# STM32F407.net
KiCad netlist of a schematic drawn in Altium Designer
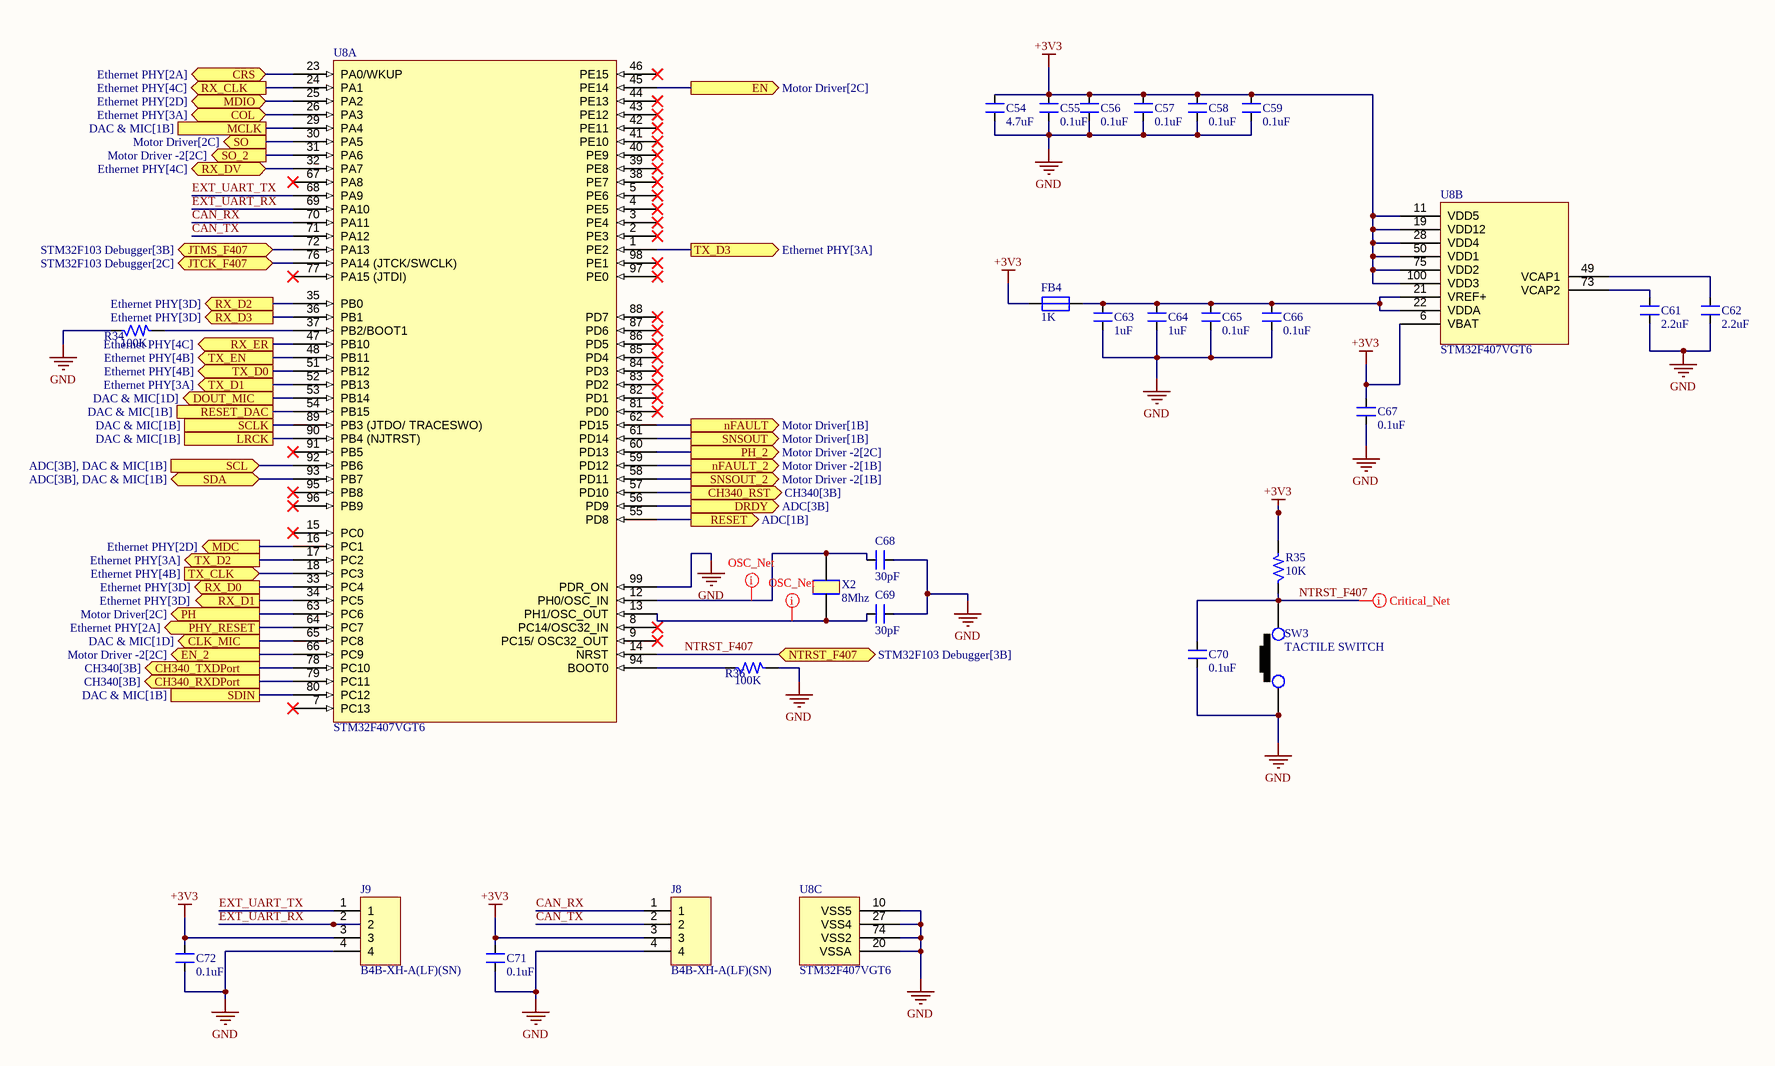
[diagram p0: STM32F407.SchDoc]

(export (version "E")
  (design (tool "Eeschema 10.0.6"))
  (components
    (comp (ref "C54")
      (value "4.7uF")
      (footprint "CAP_0805")
      (description "4.7µF ±10% 50V Ceramic Capacitor X5R 0805 (2012 Metric)")
      (fields
        (field (name "MANUFACTURER") "Yageo")
        (field (name "MANUFACTURER PART NUMBER") "GRM21BR61H475KE51L")
      )
      (libsource (lib "ESTEEMPCBLIB") (part "CAP_4.7uF-50V-10%-0805"))
    )
    (comp (ref "C55")
      (value "0.1uF")
      (footprint "CAP_0805")
      (description "0.1µF ±10% 50V Ceramic Capacitor X7R 0805 (2012 Metric)")
      (fields
        (field (name "MANUFACTURER") "Samsung")
        (field (name "MANUFACTURER PART NUMBER") "CL21B104KBCNNNC")
      )
      (libsource (lib "ESTEEMPCBLIB") (part "CAP_0.1uF-50V-10%-0805"))
    )
    (comp (ref "C56")
      (value "0.1uF")
      (footprint "CAP_0805")
      (description "0.1µF ±10% 50V Ceramic Capacitor X7R 0805 (2012 Metric)")
      (fields
        (field (name "MANUFACTURER") "Samsung")
        (field (name "MANUFACTURER PART NUMBER") "CL21B104KBCNNNC")
      )
      (libsource (lib "ESTEEMPCBLIB") (part "CAP_0.1uF-50V-10%-0805"))
    )
    (comp (ref "C57")
      (value "0.1uF")
      (footprint "CAP_0805")
      (description "0.1µF ±10% 50V Ceramic Capacitor X7R 0805 (2012 Metric)")
      (fields
        (field (name "MANUFACTURER") "Samsung")
        (field (name "MANUFACTURER PART NUMBER") "CL21B104KBCNNNC")
      )
      (libsource (lib "ESTEEMPCBLIB") (part "CAP_0.1uF-50V-10%-0805"))
    )
    (comp (ref "C58")
      (value "0.1uF")
      (footprint "CAP_0805")
      (description "0.1µF ±10% 50V Ceramic Capacitor X7R 0805 (2012 Metric)")
      (fields
        (field (name "MANUFACTURER") "Samsung")
        (field (name "MANUFACTURER PART NUMBER") "CL21B104KBCNNNC")
      )
      (libsource (lib "ESTEEMPCBLIB") (part "CAP_0.1uF-50V-10%-0805"))
    )
    (comp (ref "C59")
      (value "0.1uF")
      (footprint "CAP_0805")
      (description "0.1µF ±10% 50V Ceramic Capacitor X7R 0805 (2012 Metric)")
      (fields
        (field (name "MANUFACTURER") "Samsung")
        (field (name "MANUFACTURER PART NUMBER") "CL21B104KBCNNNC")
      )
      (libsource (lib "ESTEEMPCBLIB") (part "CAP_0.1uF-50V-10%-0805"))
    )
    (comp (ref "C61")
      (value "2.2uF")
      (footprint "CAP_0805")
      (description "2.2µF ±10% 25V Ceramic Capacitor X7R 0805 (2012 Metric)")
      (fields
        (field (name "MANUFACTURER") "KEMET")
        (field (name "MANUFACTURER PART NUMBER") "CL21B225KAFNFNE")
      )
      (libsource (lib "ESTEEMPCBLIB") (part "CAP_2.2uF-25V-10%-0805"))
    )
    (comp (ref "C62")
      (value "2.2uF")
      (footprint "CAP_0805")
      (description "2.2µF ±10% 25V Ceramic Capacitor X7R 0805 (2012 Metric)")
      (fields
        (field (name "MANUFACTURER") "KEMET")
        (field (name "MANUFACTURER PART NUMBER") "CL21B225KAFNFNE")
      )
      (libsource (lib "ESTEEMPCBLIB") (part "CAP_2.2uF-25V-10%-0805"))
    )
    (comp (ref "C63")
      (value "1uF")
      (footprint "CAP_0805")
      (description "1µF ±5% 50V Ceramic Capacitor X7R 0805 (2012 Metric)")
      (fields
        (field (name "MANUFACTURER") "Samsung")
        (field (name "MANUFACTURER PART NUMBER") "CC0805JKX7R9BB105")
      )
      (libsource (lib "ESTEEMPCBLIB") (part "CAP_1uF-50V-5%-0805"))
    )
    (comp (ref "C64")
      (value "1uF")
      (footprint "CAP_0805")
      (description "1µF ±5% 50V Ceramic Capacitor X7R 0805 (2012 Metric)")
      (fields
        (field (name "MANUFACTURER") "Samsung")
        (field (name "MANUFACTURER PART NUMBER") "CC0805JKX7R9BB105")
      )
      (libsource (lib "ESTEEMPCBLIB") (part "CAP_1uF-50V-5%-0805"))
    )
    (comp (ref "C65")
      (value "0.1uF")
      (footprint "CAP_0805")
      (description "0.1µF ±10% 50V Ceramic Capacitor X7R 0805 (2012 Metric)")
      (fields
        (field (name "MANUFACTURER") "Samsung")
        (field (name "MANUFACTURER PART NUMBER") "CL21B104KBCNNNC")
      )
      (libsource (lib "ESTEEMPCBLIB") (part "CAP_0.1uF-50V-10%-0805"))
    )
    (comp (ref "C66")
      (value "0.1uF")
      (footprint "CAP_0805")
      (description "0.1µF ±10% 50V Ceramic Capacitor X7R 0805 (2012 Metric)")
      (fields
        (field (name "MANUFACTURER") "Samsung")
        (field (name "MANUFACTURER PART NUMBER") "CL21B104KBCNNNC")
      )
      (libsource (lib "ESTEEMPCBLIB") (part "CAP_0.1uF-50V-10%-0805"))
    )
    (comp (ref "C67")
      (value "0.1uF")
      (footprint "CAP_0805")
      (description "0.1µF ±10% 50V Ceramic Capacitor X7R 0805 (2012 Metric)")
      (fields
        (field (name "MANUFACTURER") "Samsung")
        (field (name "MANUFACTURER PART NUMBER") "CL21B104KBCNNNC")
      )
      (libsource (lib "ESTEEMPCBLIB") (part "CAP_0.1uF-50V-10%-0805"))
    )
    (comp (ref "C68")
      (value "30pF")
      (footprint "CAP_0805")
      (description "±10% 50V Ceramic Capacitor C0G, NP0 0805 (2012 Metric)")
      (fields
        (field (name "MANUFACTURER PART NUMBER") "C0805C300K5GAC7800")
        (field (name "MANUFACTURER") "KEMET")
      )
      (libsource (lib "ESTEEMPCBLIB") (part "CAP_30pF-50V-10%-0805"))
    )
    (comp (ref "C69")
      (value "30pF")
      (footprint "CAP_0805")
      (description "±10% 50V Ceramic Capacitor C0G, NP0 0805 (2012 Metric)")
      (fields
        (field (name "MANUFACTURER PART NUMBER") "C0805C300K5GAC7800")
        (field (name "MANUFACTURER") "KEMET")
      )
      (libsource (lib "ESTEEMPCBLIB") (part "CAP_30pF-50V-10%-0805"))
    )
    (comp (ref "C70")
      (value "0.1uF")
      (footprint "CAP_0805")
      (description "0.1µF ±10% 50V Ceramic Capacitor X7R 0805 (2012 Metric)")
      (fields
        (field (name "MANUFACTURER") "Samsung")
        (field (name "MANUFACTURER PART NUMBER") "CL21B104KBCNNNC")
      )
      (libsource (lib "ESTEEMPCBLIB") (part "CAP_0.1uF-50V-10%-0805"))
    )
    (comp (ref "C71")
      (value "0.1uF")
      (footprint "CAP_0805")
      (description "0.1µF ±10% 50V Ceramic Capacitor X7R 0805 (2012 Metric)")
      (fields
        (field (name "MANUFACTURER") "Samsung")
        (field (name "MANUFACTURER PART NUMBER") "CL21B104KBCNNNC")
      )
      (libsource (lib "ESTEEMPCBLIB") (part "CAP_0.1uF-50V-10%-0805"))
    )
    (comp (ref "C72")
      (value "0.1uF")
      (footprint "CAP_0805")
      (description "0.1µF ±10% 50V Ceramic Capacitor X7R 0805 (2012 Metric)")
      (fields
        (field (name "MANUFACTURER") "Samsung")
        (field (name "MANUFACTURER PART NUMBER") "CL21B104KBCNNNC")
      )
      (libsource (lib "ESTEEMPCBLIB") (part "CAP_0.1uF-50V-10%-0805"))
    )
    (comp (ref "FB4")
      (value "1K")
      (footprint "IND_0805")
      (description "1 kOhms @ 100MHz 1 Power Line Ferrite Bead 0805 (2012 Metric) 1.6A")
      (fields
        (field (name "MANUFACTURER") "Laird")
        (field (name "MANUFACTURER PART NUMBER") "BLM21SP102SH1D")
      )
      (libsource (lib "ESTEEMPCBLIB") (part "FB_1K-100MHZ-1.6A-0805"))
    )
    (comp (ref "J8")
      (value "B4B-XH-A(LF)(SN)")
      (footprint "CON4_100_B4B-XH-A_TH_ST")
      (description "4 Pins, 1 Row 2.54mm Pitch, straight Connector, male")
      (fields (field (name "MANUFACTURER") "Wurth Electronics") (field (name "MATING PART NUMBER") "XHP-4"))
      (libsource (lib "ESTEEMPCBLIB") (part "CON-PLG_4X1-100-ST-TH"))
    )
    (comp (ref "J9")
      (value "B4B-XH-A(LF)(SN)")
      (footprint "CON4_100_B4B-XH-A_TH_ST")
      (description "4 Pins, 1 Row 2.54mm Pitch, straight Connector, male")
      (fields (field (name "MANUFACTURER") "Wurth Electronics") (field (name "MATING PART NUMBER") "XHP-4"))
      (libsource (lib "ESTEEMPCBLIB") (part "CON-PLG_4X1-100-ST-TH"))
    )
    (comp (ref "R34")
      (value "100K")
      (footprint "RES_0603")
      (description "100 kOhms ±1% 0.1W, 1/10W Chip Resistor 0603 (1608 Metric) Automotive AEC-Q200 Thick Film")
      (fields
        (field (name "MANUFACTURER") "Stackpole Electronics")
        (field (name "MANUFACTURER PART NUMBER") "RMCF0603FT100K")
      )
      (libsource (lib "ESTEEMPCBLIB") (part "RES_100K-0.1W-1%-0603"))
    )
    (comp (ref "R35")
      (value "10K")
      (footprint "RES_0603")
      (description "10 kOhms ±1% 0.1W, 1/10W Chip Resistor 0603 (1608 Metric) Automotive AEC-Q200 Thick Film")
      (fields (field (name "MANUFACTURER") "Walsin") (field (name "MANUFACTURER PART NUMBER") "WR06X1002FTL"))
      (libsource (lib "ESTEEMPCBLIB") (part "RES_10K-0.1W-1%-0603"))
    )
    (comp (ref "R36")
      (value "100K")
      (footprint "RES_0603")
      (description "100 kOhms ±1% 0.1W, 1/10W Chip Resistor 0603 (1608 Metric) Automotive AEC-Q200 Thick Film")
      (fields
        (field (name "MANUFACTURER") "Stackpole Electronics")
        (field (name "MANUFACTURER PART NUMBER") "RMCF0603FT100K")
      )
      (libsource (lib "ESTEEMPCBLIB") (part "RES_100K-0.1W-1%-0603"))
    )
    (comp (ref "SW3")
      (value "TACTILE SWITCH")
      (footprint "SW_342_SMD")
      (description "Tactile Switch SPST-NO Top Actuated Surface Mount")
      (fields
        (field (name "MANUFACTURER") "ITT C&K")
        (field (name "MANUFACTURER PART NUMBER") "RS-282G05A3-SMRT")
      )
      (libsource (lib "ESTEEMPCBLIB") (part "SW1_RS-282G05A3-SMRT-SMD"))
    )
    (comp (ref "U8")
      (value "STM32F407VGT6")
      (footprint "QFN100_19.6_669_58X10_SMD")
      (description "ARM® Cortex®-M4 STM32F4 Microcontroller IC 32-Bit 168MHz 1MB (1M x 8) FLASH 100-LQFP (14x14)")
      (fields (field (name "MANUFACTURER") "STMicroelectronics"))
      (libsource (lib "ESTEEMPCBLIB") (part "IC_STM32F407VGT6"))
    )
    (comp (ref "X2")
      (value "8Mhz")
      (footprint "XTAL_314_240X47_SMD")
      (description "8MHz ±30ppm Crystal 32pF 60 Ohms HC-49/US")
      (fields
        (field (name "MANUFACTURER") "Fox Electronics")
        (field (name "MANUFACTURER PART NUMBER") "ECS-80-32-5PX-TR")
      )
      (libsource (lib "ESTEEMPCBLIB") (part "XTAL_8MHZ-ECS-80-32-5PX-SMD"))
    )
  )
  (nets
    (net (code "1") (name "+3V3") (class "Default")
      (node (ref "C54") (pin "2") (pinfunction "2_2") (pintype "passive"))
      (node (ref "C55") (pin "2") (pinfunction "2_2") (pintype "passive"))
      (node (ref "C56") (pin "2") (pinfunction "2_2") (pintype "passive"))
      (node (ref "C57") (pin "2") (pinfunction "2_2") (pintype "passive"))
      (node (ref "C58") (pin "2") (pinfunction "2_2") (pintype "passive"))
      (node (ref "C59") (pin "2") (pinfunction "2_2") (pintype "passive"))
      (node (ref "C67") (pin "2") (pinfunction "2_2") (pintype "passive"))
      (node (ref "C71") (pin "2") (pinfunction "2_2") (pintype "passive"))
      (node (ref "C72") (pin "2") (pinfunction "2_2") (pintype "passive"))
      (node (ref "FB4") (pin "1") (pinfunction "1_1") (pintype "passive"))
      (node (ref "J8") (pin "3") (pinfunction "3_3") (pintype "passive"))
      (node (ref "J9") (pin "3") (pinfunction "3_3") (pintype "passive"))
      (node (ref "R35") (pin "2") (pinfunction "2_2") (pintype "passive"))
      (node (ref "U8") (pin "100") (pinfunction "VDD3_100") (pintype "passive"))
      (node (ref "U8") (pin "11") (pinfunction "VDD5_11") (pintype "passive"))
      (node (ref "U8") (pin "19") (pinfunction "VDD12_19") (pintype "passive"))
      (node (ref "U8") (pin "28") (pinfunction "VDD4_28") (pintype "passive"))
      (node (ref "U8") (pin "50") (pinfunction "VDD1_50") (pintype "passive"))
      (node (ref "U8") (pin "6") (pinfunction "VBAT_6") (pintype "passive"))
      (node (ref "U8") (pin "75") (pinfunction "VDD2_75") (pintype "passive"))
    )
    (net (code "2") (name "/CAN_RX") (class "Default")
      (node (ref "J8") (pin "1") (pinfunction "1_1") (pintype "passive"))
      (node (ref "U8") (pin "70") (pinfunction "PA11_70") (pintype "input"))
    )
    (net (code "3") (name "/CAN_TX") (class "Default")
      (node (ref "J8") (pin "2") (pinfunction "2_2") (pintype "passive"))
      (node (ref "U8") (pin "71") (pinfunction "PA12_71") (pintype "input"))
    )
    (net (code "4") (name "/CH340_RST") (class "Default")
      (node (ref "U8") (pin "57") (pinfunction "PD10_57") (pintype "input"))
    )
    (net (code "5") (name "/CH340_RXDPort") (class "Default")
      (node (ref "U8") (pin "79") (pinfunction "PC11_79") (pintype "input"))
    )
    (net (code "6") (name "/CH340_TXDPort") (class "Default")
      (node (ref "U8") (pin "78") (pinfunction "PC10_78") (pintype "input"))
    )
    (net (code "7") (name "/CLK_MIC") (class "Default")
      (node (ref "U8") (pin "65") (pinfunction "PC8_65") (pintype "input"))
    )
    (net (code "8") (name "/COL") (class "Default")
      (node (ref "U8") (pin "26") (pinfunction "PA3_26") (pintype "input"))
    )
    (net (code "9") (name "/CRS") (class "Default")
      (node (ref "U8") (pin "23") (pinfunction "PA0/WKUP_23") (pintype "input"))
    )
    (net (code "10") (name "/DOUT_MIC") (class "Default")
      (node (ref "U8") (pin "53") (pinfunction "PB14_53") (pintype "input"))
    )
    (net (code "11") (name "/DRDY") (class "Default")
      (node (ref "U8") (pin "56") (pinfunction "PD9_56") (pintype "input"))
    )
    (net (code "12") (name "/EN") (class "Default")
      (node (ref "U8") (pin "45") (pinfunction "PE14_45") (pintype "input"))
    )
    (net (code "13") (name "/EN_2") (class "Default")
      (node (ref "U8") (pin "66") (pinfunction "PC9_66") (pintype "input"))
    )
    (net (code "14") (name "/EXT_UART_RX") (class "Default")
      (node (ref "J9") (pin "2") (pinfunction "2_2") (pintype "passive"))
      (node (ref "U8") (pin "69") (pinfunction "PA10_69") (pintype "input"))
    )
    (net (code "15") (name "/EXT_UART_TX") (class "Default")
      (node (ref "J9") (pin "1") (pinfunction "1_1") (pintype "passive"))
      (node (ref "U8") (pin "68") (pinfunction "PA9_68") (pintype "input"))
    )
    (net (code "16") (name "/JTCK_F407") (class "Default")
      (node (ref "U8") (pin "76") (pinfunction "PA14_(JTCK/SWCLK)_76") (pintype "input"))
    )
    (net (code "17") (name "/JTMS_F407") (class "Default")
      (node (ref "U8") (pin "72") (pinfunction "PA13_72") (pintype "input"))
    )
    (net (code "18") (name "/LRCK") (class "Default")
      (node (ref "U8") (pin "90") (pinfunction "PB4_(NJTRST)_90") (pintype "input"))
    )
    (net (code "19") (name "/MCLK") (class "Default")
      (node (ref "U8") (pin "29") (pinfunction "PA4_29") (pintype "input"))
    )
    (net (code "20") (name "/MDC") (class "Default")
      (node (ref "U8") (pin "16") (pinfunction "PC1_16") (pintype "input"))
    )
    (net (code "21") (name "/MDIO") (class "Default")
      (node (ref "U8") (pin "25") (pinfunction "PA2_25") (pintype "input"))
    )
    (net (code "22") (name "/NTRST_F407") (class "Default")
      (node (ref "C70") (pin "2") (pinfunction "2_2") (pintype "passive"))
      (node (ref "R35") (pin "1") (pinfunction "1_1") (pintype "passive"))
      (node (ref "SW3") (pin "2") (pinfunction "2_2") (pintype "passive"))
      (node (ref "U8") (pin "14") (pinfunction "NRST_14") (pintype "input"))
    )
    (net (code "23") (name "/PH") (class "Default")
      (node (ref "U8") (pin "63") (pinfunction "PC6_63") (pintype "input"))
    )
    (net (code "24") (name "/PHY_RESET") (class "Default")
      (node (ref "U8") (pin "64") (pinfunction "PC7_64") (pintype "input"))
    )
    (net (code "25") (name "/PH_2") (class "Default")
      (node (ref "U8") (pin "60") (pinfunction "PD13_60") (pintype "input"))
    )
    (net (code "26") (name "/RESET") (class "Default")
      (node (ref "U8") (pin "55") (pinfunction "PD8_55") (pintype "input"))
    )
    (net (code "27") (name "/RESET_DAC") (class "Default")
      (node (ref "U8") (pin "54") (pinfunction "PB15_54") (pintype "input"))
    )
    (net (code "28") (name "/RX_CLK") (class "Default")
      (node (ref "U8") (pin "24") (pinfunction "PA1_24") (pintype "input"))
    )
    (net (code "29") (name "/RX_D0") (class "Default")
      (node (ref "U8") (pin "33") (pinfunction "PC4_33") (pintype "input"))
    )
    (net (code "30") (name "/RX_D1") (class "Default")
      (node (ref "U8") (pin "34") (pinfunction "PC5_34") (pintype "input"))
    )
    (net (code "31") (name "/RX_D2") (class "Default")
      (node (ref "U8") (pin "35") (pinfunction "PB0_35") (pintype "input"))
    )
    (net (code "32") (name "/RX_D3") (class "Default")
      (node (ref "U8") (pin "36") (pinfunction "PB1_36") (pintype "input"))
    )
    (net (code "33") (name "/RX_DV") (class "Default")
      (node (ref "U8") (pin "32") (pinfunction "PA7_32") (pintype "input"))
    )
    (net (code "34") (name "/RX_ER") (class "Default")
      (node (ref "U8") (pin "47") (pinfunction "PB10_47") (pintype "input"))
    )
    (net (code "35") (name "/SCL") (class "Default")
      (node (ref "U8") (pin "92") (pinfunction "PB6_92") (pintype "input"))
    )
    (net (code "36") (name "/SCLK") (class "Default")
      (node (ref "U8") (pin "89") (pinfunction "PB3_(JTDO/_TRACESWO)_89") (pintype "input"))
    )
    (net (code "37") (name "/SDA") (class "Default")
      (node (ref "U8") (pin "93") (pinfunction "PB7_93") (pintype "input"))
    )
    (net (code "38") (name "/SDIN") (class "Default")
      (node (ref "U8") (pin "80") (pinfunction "PC12_80") (pintype "input"))
    )
    (net (code "39") (name "/SNSOUT") (class "Default")
      (node (ref "U8") (pin "61") (pinfunction "PD14_61") (pintype "input"))
    )
    (net (code "40") (name "/SNSOUT_2") (class "Default")
      (node (ref "U8") (pin "58") (pinfunction "PD11_58") (pintype "input"))
    )
    (net (code "41") (name "/SO") (class "Default")
      (node (ref "U8") (pin "30") (pinfunction "PA5_30") (pintype "input"))
    )
    (net (code "42") (name "/SO_2") (class "Default")
      (node (ref "U8") (pin "31") (pinfunction "PA6_31") (pintype "input"))
    )
    (net (code "43") (name "/TX_CLK") (class "Default")
      (node (ref "U8") (pin "18") (pinfunction "PC3_18") (pintype "input"))
    )
    (net (code "44") (name "/TX_D0") (class "Default")
      (node (ref "U8") (pin "51") (pinfunction "PB12_51") (pintype "input"))
    )
    (net (code "45") (name "/TX_D1") (class "Default")
      (node (ref "U8") (pin "52") (pinfunction "PB13_52") (pintype "input"))
    )
    (net (code "46") (name "/TX_D2") (class "Default")
      (node (ref "U8") (pin "17") (pinfunction "PC2_17") (pintype "input"))
    )
    (net (code "47") (name "/TX_D3") (class "Default")
      (node (ref "U8") (pin "1") (pinfunction "PE2_1") (pintype "input"))
    )
    (net (code "48") (name "/TX_EN") (class "Default")
      (node (ref "U8") (pin "48") (pinfunction "PB11_48") (pintype "input"))
    )
    (net (code "49") (name "/nFAULT") (class "Default")
      (node (ref "U8") (pin "62") (pinfunction "PD15_62") (pintype "input"))
    )
    (net (code "50") (name "/nFAULT_2") (class "Default")
      (node (ref "U8") (pin "59") (pinfunction "PD12_59") (pintype "input"))
    )
    (net (code "51") (name "GND") (class "Default")
      (node (ref "C54") (pin "1") (pinfunction "1_1") (pintype "passive"))
      (node (ref "C55") (pin "1") (pinfunction "1_1") (pintype "passive"))
      (node (ref "C56") (pin "1") (pinfunction "1_1") (pintype "passive"))
      (node (ref "C57") (pin "1") (pinfunction "1_1") (pintype "passive"))
      (node (ref "C58") (pin "1") (pinfunction "1_1") (pintype "passive"))
      (node (ref "C59") (pin "1") (pinfunction "1_1") (pintype "passive"))
      (node (ref "C61") (pin "1") (pinfunction "1_1") (pintype "passive"))
      (node (ref "C62") (pin "1") (pinfunction "1_1") (pintype "passive"))
      (node (ref "C63") (pin "1") (pinfunction "1_1") (pintype "passive"))
      (node (ref "C64") (pin "1") (pinfunction "1_1") (pintype "passive"))
      (node (ref "C65") (pin "1") (pinfunction "1_1") (pintype "passive"))
      (node (ref "C66") (pin "1") (pinfunction "1_1") (pintype "passive"))
      (node (ref "C67") (pin "1") (pinfunction "1_1") (pintype "passive"))
      (node (ref "C68") (pin "2") (pinfunction "2_2") (pintype "passive"))
      (node (ref "C69") (pin "2") (pinfunction "2_2") (pintype "passive"))
      (node (ref "C70") (pin "1") (pinfunction "1_1") (pintype "passive"))
      (node (ref "C71") (pin "1") (pinfunction "1_1") (pintype "passive"))
      (node (ref "C72") (pin "1") (pinfunction "1_1") (pintype "passive"))
      (node (ref "J8") (pin "4") (pinfunction "4_4") (pintype "passive"))
      (node (ref "J9") (pin "4") (pinfunction "4_4") (pintype "passive"))
      (node (ref "R34") (pin "1") (pinfunction "1_1") (pintype "passive"))
      (node (ref "R36") (pin "2") (pinfunction "2_2") (pintype "passive"))
      (node (ref "SW3") (pin "1") (pinfunction "1_1") (pintype "passive"))
      (node (ref "U8") (pin "10") (pinfunction "VSS5_10") (pintype "passive"))
      (node (ref "U8") (pin "20") (pinfunction "VSSA_20") (pintype "passive"))
      (node (ref "U8") (pin "27") (pinfunction "VSS4_27") (pintype "passive"))
      (node (ref "U8") (pin "74") (pinfunction "VSS2_74") (pintype "passive"))
      (node (ref "U8") (pin "99") (pinfunction "PDR_ON_99") (pintype "input"))
    )
    (net (code "52") (name "Net-(U8A-BOOT0)") (class "Default")
      (node (ref "R36") (pin "1") (pinfunction "1_1") (pintype "passive"))
      (node (ref "U8") (pin "94") (pinfunction "BOOT0_94") (pintype "input"))
    )
    (net (code "53") (name "Net-(U8A-PB2{slash}BOOT1)") (class "Default")
      (node (ref "R34") (pin "2") (pinfunction "2_2") (pintype "passive"))
      (node (ref "U8") (pin "37") (pinfunction "PB2/BOOT1_37") (pintype "input"))
    )
    (net (code "54") (name "Net-(U8A-PH0{slash}OSC_IN)") (class "Default")
      (node (ref "C68") (pin "1") (pinfunction "1_1") (pintype "passive"))
      (node (ref "U8") (pin "12") (pinfunction "PH0/OSC_IN_12") (pintype "input"))
      (node (ref "X2") (pin "2") (pinfunction "2_2") (pintype "passive"))
    )
    (net (code "55") (name "Net-(U8A-PH1{slash}OSC_OUT)") (class "Default")
      (node (ref "C69") (pin "1") (pinfunction "1_1") (pintype "passive"))
      (node (ref "U8") (pin "13") (pinfunction "PH1/OSC_OUT_13") (pintype "input"))
      (node (ref "X2") (pin "1") (pinfunction "1_1") (pintype "passive"))
    )
    (net (code "56") (name "Net-(U8B-VCAP1)") (class "Default")
      (node (ref "C62") (pin "2") (pinfunction "2_2") (pintype "passive"))
      (node (ref "U8") (pin "49") (pinfunction "VCAP1_49") (pintype "passive"))
    )
    (net (code "57") (name "Net-(U8B-VCAP2)") (class "Default")
      (node (ref "C61") (pin "2") (pinfunction "2_2") (pintype "passive"))
      (node (ref "U8") (pin "73") (pinfunction "VCAP2_73") (pintype "passive"))
    )
    (net (code "58") (name "Net-(U8B-VDDA)") (class "Default")
      (node (ref "C63") (pin "2") (pinfunction "2_2") (pintype "passive"))
      (node (ref "C64") (pin "2") (pinfunction "2_2") (pintype "passive"))
      (node (ref "C65") (pin "2") (pinfunction "2_2") (pintype "passive"))
      (node (ref "C66") (pin "2") (pinfunction "2_2") (pintype "passive"))
      (node (ref "FB4") (pin "2") (pinfunction "2_2") (pintype "passive"))
      (node (ref "U8") (pin "21") (pinfunction "VREF+_21") (pintype "passive"))
      (node (ref "U8") (pin "22") (pinfunction "VDDA_22") (pintype "passive"))
    )
    (net (code "59") (name "unconnected-(U8A-PA8-Pad67)") (class "Default")
      (node (ref "U8") (pin "67") (pinfunction "PA8_67") (pintype "input+no_connect"))
    )
    (net (code "60") (name "unconnected-(U8A-PA15_(JTDI)-Pad77)") (class "Default")
      (node (ref "U8") (pin "77") (pinfunction "PA15_(JTDI)_77") (pintype "input+no_connect"))
    )
    (net (code "61") (name "unconnected-(U8A-PB5-Pad91)") (class "Default")
      (node (ref "U8") (pin "91") (pinfunction "PB5_91") (pintype "input+no_connect"))
    )
    (net (code "62") (name "unconnected-(U8A-PB8-Pad95)") (class "Default")
      (node (ref "U8") (pin "95") (pinfunction "PB8_95") (pintype "input+no_connect"))
    )
    (net (code "63") (name "unconnected-(U8A-PB9-Pad96)") (class "Default")
      (node (ref "U8") (pin "96") (pinfunction "PB9_96") (pintype "input+no_connect"))
    )
    (net (code "64") (name "unconnected-(U8A-PC0-Pad15)") (class "Default")
      (node (ref "U8") (pin "15") (pinfunction "PC0_15") (pintype "input+no_connect"))
    )
    (net (code "65") (name "unconnected-(U8A-PC13-Pad7)") (class "Default")
      (node (ref "U8") (pin "7") (pinfunction "PC13_7") (pintype "input+no_connect"))
    )
    (net (code "66") (name "unconnected-(U8A-PC14{slash}OSC32_IN-Pad8)") (class "Default")
      (node (ref "U8") (pin "8") (pinfunction "PC14/OSC32_IN_8") (pintype "input+no_connect"))
    )
    (net (code "67") (name "unconnected-(U8A-PC15{slash}_OSC32_OUT-Pad9)") (class "Default")
      (node (ref "U8") (pin "9") (pinfunction "PC15/_OSC32_OUT_9") (pintype "input+no_connect"))
    )
    (net (code "68") (name "unconnected-(U8A-PD0-Pad81)") (class "Default")
      (node (ref "U8") (pin "81") (pinfunction "PD0_81") (pintype "input+no_connect"))
    )
    (net (code "69") (name "unconnected-(U8A-PD1-Pad82)") (class "Default")
      (node (ref "U8") (pin "82") (pinfunction "PD1_82") (pintype "input+no_connect"))
    )
    (net (code "70") (name "unconnected-(U8A-PD2-Pad83)") (class "Default")
      (node (ref "U8") (pin "83") (pinfunction "PD2_83") (pintype "input+no_connect"))
    )
    (net (code "71") (name "unconnected-(U8A-PD3-Pad84)") (class "Default")
      (node (ref "U8") (pin "84") (pinfunction "PD3_84") (pintype "input+no_connect"))
    )
    (net (code "72") (name "unconnected-(U8A-PD4-Pad85)") (class "Default")
      (node (ref "U8") (pin "85") (pinfunction "PD4_85") (pintype "input+no_connect"))
    )
    (net (code "73") (name "unconnected-(U8A-PD5-Pad86)") (class "Default")
      (node (ref "U8") (pin "86") (pinfunction "PD5_86") (pintype "input+no_connect"))
    )
    (net (code "74") (name "unconnected-(U8A-PD6-Pad87)") (class "Default")
      (node (ref "U8") (pin "87") (pinfunction "PD6_87") (pintype "input+no_connect"))
    )
    (net (code "75") (name "unconnected-(U8A-PD7-Pad88)") (class "Default")
      (node (ref "U8") (pin "88") (pinfunction "PD7_88") (pintype "input+no_connect"))
    )
    (net (code "76") (name "unconnected-(U8A-PE0-Pad97)") (class "Default")
      (node (ref "U8") (pin "97") (pinfunction "PE0_97") (pintype "input+no_connect"))
    )
    (net (code "77") (name "unconnected-(U8A-PE1-Pad98)") (class "Default")
      (node (ref "U8") (pin "98") (pinfunction "PE1_98") (pintype "input+no_connect"))
    )
    (net (code "78") (name "unconnected-(U8A-PE3-Pad2)") (class "Default")
      (node (ref "U8") (pin "2") (pinfunction "PE3_2") (pintype "input+no_connect"))
    )
    (net (code "79") (name "unconnected-(U8A-PE4-Pad3)") (class "Default")
      (node (ref "U8") (pin "3") (pinfunction "PE4_3") (pintype "input+no_connect"))
    )
    (net (code "80") (name "unconnected-(U8A-PE5-Pad4)") (class "Default")
      (node (ref "U8") (pin "4") (pinfunction "PE5_4") (pintype "input+no_connect"))
    )
    (net (code "81") (name "unconnected-(U8A-PE6-Pad5)") (class "Default")
      (node (ref "U8") (pin "5") (pinfunction "PE6_5") (pintype "input+no_connect"))
    )
    (net (code "82") (name "unconnected-(U8A-PE7-Pad38)") (class "Default")
      (node (ref "U8") (pin "38") (pinfunction "PE7_38") (pintype "input+no_connect"))
    )
    (net (code "83") (name "unconnected-(U8A-PE8-Pad39)") (class "Default")
      (node (ref "U8") (pin "39") (pinfunction "PE8_39") (pintype "input+no_connect"))
    )
    (net (code "84") (name "unconnected-(U8A-PE9-Pad40)") (class "Default")
      (node (ref "U8") (pin "40") (pinfunction "PE9_40") (pintype "input+no_connect"))
    )
    (net (code "85") (name "unconnected-(U8A-PE10-Pad41)") (class "Default")
      (node (ref "U8") (pin "41") (pinfunction "PE10_41") (pintype "input+no_connect"))
    )
    (net (code "86") (name "unconnected-(U8A-PE11-Pad42)") (class "Default")
      (node (ref "U8") (pin "42") (pinfunction "PE11_42") (pintype "input+no_connect"))
    )
    (net (code "87") (name "unconnected-(U8A-PE12-Pad43)") (class "Default")
      (node (ref "U8") (pin "43") (pinfunction "PE12_43") (pintype "input+no_connect"))
    )
    (net (code "88") (name "unconnected-(U8A-PE13-Pad44)") (class "Default")
      (node (ref "U8") (pin "44") (pinfunction "PE13_44") (pintype "input+no_connect"))
    )
    (net (code "89") (name "unconnected-(U8A-PE15-Pad46)") (class "Default")
      (node (ref "U8") (pin "46") (pinfunction "PE15_46") (pintype "input+no_connect"))
    )
  )
)
